# Sheet1.net
KiCad netlist of a schematic drawn in Altium Designer
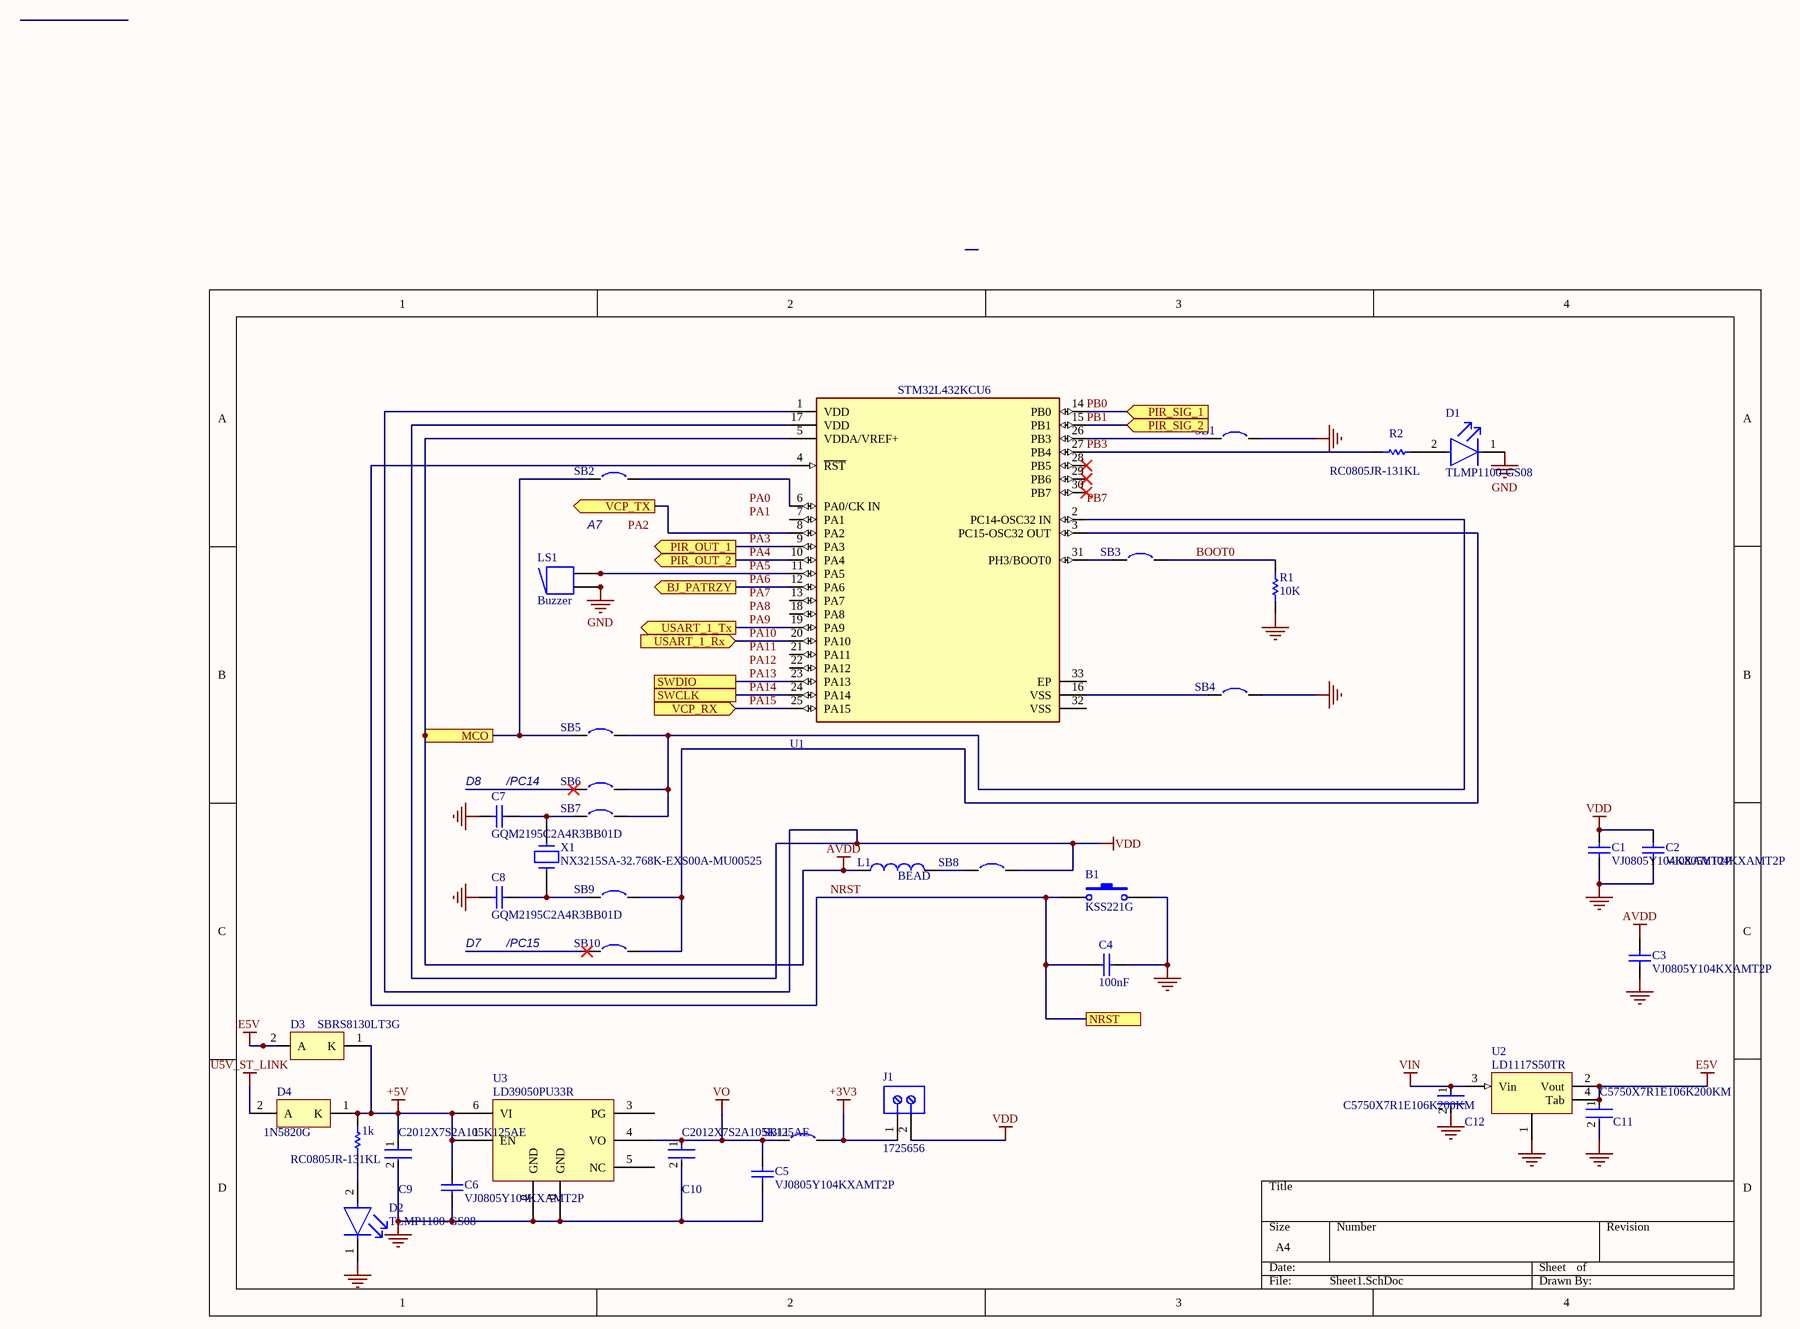
[diagram p0: Sheet1.SchDoc]

(export (version "E")
  (design (tool "Eeschema 10.0.6"))
  (components
    (comp (ref "1k")
      (value "RC0805JR-131KL")
      (footprint "RESC2013X60X35ML10T20")
      (fields (field (name "MANUFACTURER") "Yageo"))
      (libsource (lib "Altium Content Vault") (part "RES"))
    )
    (comp (ref "B1")
      (value "KSS221G")
      (footprint "SW2_5R6_5R5x3R1")
      (description "Switch")
      (fields (field (name "PUBLISHER") "Altium Limited"))
      (libsource (lib "Miscellaneous Devices") (part "SW-PB"))
    )
    (comp (ref "C1")
      (value "VJ0805Y104KXAMT2P")
      (footprint "CAPC2013X145X48NL20T23")
      (fields (field (name "MANUFACTURER") "Vishay"))
      (libsource (lib "Altium Content Vault") (part "CMP-2007-02027-1"))
    )
    (comp (ref "C2")
      (value "VJ0805Y104KXAMT2P")
      (footprint "CAPC2013X145X48NL20T23")
      (fields (field (name "MANUFACTURER") "Vishay"))
      (libsource (lib "Altium Content Vault") (part "CMP-2007-02027-1"))
    )
    (comp (ref "C3")
      (value "VJ0805Y104KXAMT2P")
      (footprint "CAPC2013X145X48NL20T23")
      (fields (field (name "MANUFACTURER") "Vishay"))
      (libsource (lib "Altium Content Vault") (part "CMP-2007-02027-1"))
    )
    (comp (ref "C4")
      (value "100nF")
      (footprint "0603C")
      (description "Capacitor")
      (fields (field (name "PUBLISHER") "Altium Limited"))
      (libsource (lib "Miscellaneous Devices") (part "CAP"))
    )
    (comp (ref "C5")
      (value "VJ0805Y104KXAMT2P")
      (footprint "CAPC2013X145X48NL20T23")
      (fields (field (name "MANUFACTURER") "Vishay"))
      (libsource (lib "Altium Content Vault") (part "CMP-2007-02027-1"))
    )
    (comp (ref "C6")
      (value "VJ0805Y104KXAMT2P")
      (footprint "CAPC2013X145X48NL20T23")
      (fields (field (name "MANUFACTURER") "Vishay"))
      (libsource (lib "Altium Content Vault") (part "CMP-2007-02027-1"))
    )
    (comp (ref "C7")
      (value "GQM2195C2A4R3BB01D")
      (footprint "CAPC2013X100X45LL15T25")
      (fields (field (name "MANUFACTURER") "Murata"))
      (libsource (lib "Altium Content Vault") (part "CMP-2007-03772-1"))
    )
    (comp (ref "C8")
      (value "GQM2195C2A4R3BB01D")
      (footprint "CAPC2013X100X45LL15T25")
      (fields (field (name "MANUFACTURER") "Murata"))
      (libsource (lib "Altium Content Vault") (part "CMP-2007-03772-1"))
    )
    (comp (ref "C9")
      (value "C2012X7S2A105K125AE")
      (footprint "FP-C2012-125-IPC_B")
      (description "CAP CER 1UF 100V X7S 0805")
      (fields (field (name "TOLERANCE") "10%"))
      (libsource (lib "Altium Content Vault") (part "CMP-08246-004333-1"))
    )
    (comp (ref "C10")
      (value "C2012X7S2A105K125AE")
      (footprint "FP-C2012-125-IPC_B")
      (description "CAP CER 1UF 100V X7S 0805")
      (fields (field (name "TOLERANCE") "10%"))
      (libsource (lib "Altium Content Vault") (part "CMP-08246-004333-1"))
    )
    (comp (ref "C11")
      (value "C5750X7R1E106K200KM")
      (footprint "FP-C5750-200-0_4-IPC_A")
      (description "Multilayer Ceramic Capacitors 10uF ±10% 25V X7R SMD 2220")
      (fields (field (name "TOLERANCE") "10%"))
      (libsource (lib "Altium Content Vault") (part "CMP-08246-006659-1"))
    )
    (comp (ref "C12")
      (value "C5750X7R1E106K200KM")
      (footprint "FP-C5750-200-0_4-IPC_A")
      (description "Multilayer Ceramic Capacitors 10uF ±10% 25V X7R SMD 2220")
      (fields (field (name "TOLERANCE") "10%"))
      (libsource (lib "Altium Content Vault") (part "CMP-08246-006659-1"))
    )
    (comp (ref "D1")
      (value "TLMP1100-GS08")
      (footprint "FP-6_541-5056_01-4-MFG")
      (description "Green 561nm LED Indication - Discrete 2.1V 0603 (1608 Metric)")
      (fields (field (name "MANUFACTURER") "Vishay"))
      (libsource (lib "Altium Content Vault") (part "8706943c75ba83719d021d2fdc84c58"))
    )
    (comp (ref "D2")
      (value "TLMP1100-GS08")
      (footprint "FP-6_541-5056_01-4-MFG")
      (description "LED GREEN 0603 SMD")
      (fields
        (field (name "MANUFACTURER") "Vishay")
        (field (name "OCTOPART") "https://octopart.com/tlmp1100-gs08-vishay-55433993")
      )
      (libsource (lib "Components - 19.01.23 - 11.56") (part "CMP-02520-000009-1"))
    )
    (comp (ref "D3")
      (value "SBRS8130LT3G")
      (footprint "ONSC-SMB-2-403A-03_H_V")
      (description "Schottky Power Rectifier, 2-Pin SMB, Pb-Free, Tape and Reel")
      (fields (field (name "MANUFACTURER") "On Semiconductor"))
      (libsource (lib "Altium Content Vault") (part "CMP-1055-00345-1"))
    )
    (comp (ref "D4")
      (value "1N5820G")
      (footprint "ONSC-AXIAL_LEAD-2-267-05_V")
      (description "Rectifier, 2-Pin Axial_Lead, Pb-Free, Bulk Bag")
      (fields (field (name "MANUFACTURER") "On Semiconductor"))
      (libsource (lib "Altium Content Vault") (part "CMP-1055-00026-1"))
    )
    (comp (ref "J1")
      (value "1725656")
      (footprint "PHOE-1725656-2")
      (description "Male Header, Pitch 2.54 mm, 1 x 2 Position, Height 9 mm, Tail Length 3.5 mm")
      (fields (field (name "MANUFACTURER") "Phoenix Contact"))
      (libsource (lib "Altium Content Vault") (part "CMP-2000-05299-1"))
    )
    (comp (ref "L1")
      (value "BEAD")
      (footprint "0603L")
      (description "Inductor")
      (fields (field (name "PUBLISHER") "Altium Limited"))
      (libsource (lib "Miscellaneous Devices") (part "Inductor"))
    )
    (comp (ref "LS1")
      (value "Buzzer")
      (footprint "ABSM-1574")
      (description "Magnetic Transducer Buzzer")
      (fields (field (name "PUBLISHER") "Altium Limited"))
      (libsource (lib "Miscellaneous Devices") (part "Buzzer"))
    )
    (comp (ref "R1")
      (value "10K")
      (footprint "0603R")
      (description "Resistor")
      (fields (field (name "PUBLISHER") "Altium Limited"))
      (libsource (lib "Miscellaneous Devices") (part "res1"))
    )
    (comp (ref "R2")
      (value "RC0805JR-131KL")
      (footprint "RESC2013X60X35ML10T20")
      (fields (field (name "MANUFACTURER") "Yageo"))
      (libsource (lib "Altium Content Vault") (part "RES"))
    )
    (comp (ref "SB1")
      (value "Circuit Breaker (close)")
      (footprint "SB_0603")
      (description "Circuit Breaker")
      (fields (field (name "PUBLISHER") "Altium Limited"))
      (libsource (lib "MCD_TOOLS") (part "Circuit Breaker"))
    )
    (comp (ref "SB2")
      (value "Circuit Breaker (open)")
      (footprint "SB_0603")
      (description "Circuit Breaker")
      (fields (field (name "PUBLISHER") "Altium Limited"))
      (libsource (lib "MCD_TOOLS") (part "Circuit Breaker"))
    )
    (comp (ref "SB3")
      (value "Circuit Breaker (close)")
      (footprint "SB_0603")
      (description "Circuit Breaker")
      (fields (field (name "PUBLISHER") "Altium Limited"))
      (libsource (lib "MCD_TOOLS") (part "Circuit Breaker"))
    )
    (comp (ref "SB4")
      (value "Circuit Breaker (close)")
      (footprint "SB_0603")
      (description "Circuit Breaker")
      (fields (field (name "PUBLISHER") "Altium Limited"))
      (libsource (lib "MCD_TOOLS") (part "Circuit Breaker"))
    )
    (comp (ref "SB5")
      (value "Circuit Breaker (open)")
      (footprint "SB_0603")
      (description "Circuit Breaker")
      (fields (field (name "PUBLISHER") "Altium Limited"))
      (libsource (lib "MCD_TOOLS") (part "Circuit Breaker"))
    )
    (comp (ref "SB6")
      (value "Circuit Breaker")
      (footprint "SB_0603")
      (fields (field (name "PUBLISHER") "Altium Limited"))
      (libsource (lib "MCD_TOOLS") (part "Circuit Breaker"))
    )
    (comp (ref "SB7")
      (value "Circuit Breaker")
      (footprint "SB_0603")
      (fields (field (name "PUBLISHER") "Altium Limited"))
      (libsource (lib "MCD_TOOLS") (part "Circuit Breaker"))
    )
    (comp (ref "SB8")
      (value "Circuit Breaker (close)")
      (footprint "SB_0603")
      (description "Circuit Breaker")
      (fields (field (name "PUBLISHER") "Altium Limited"))
      (libsource (lib "MCD_TOOLS") (part "Circuit Breaker"))
    )
    (comp (ref "SB9")
      (value "Circuit Breaker")
      (footprint "SB_0603")
      (fields (field (name "PUBLISHER") "Altium Limited"))
      (libsource (lib "MCD_TOOLS") (part "Circuit Breaker"))
    )
    (comp (ref "SB10")
      (value "Circuit Breaker")
      (footprint "SB_0603")
      (fields (field (name "PUBLISHER") "Altium Limited"))
      (libsource (lib "MCD_TOOLS") (part "Circuit Breaker"))
    )
    (comp (ref "SB11")
      (value "Circuit Breaker (close)")
      (footprint "SB_0603")
      (description "Circuit Breaker")
      (fields (field (name "PUBLISHER") "Altium Limited"))
      (libsource (lib "MCD_TOOLS") (part "Circuit Breaker"))
    )
    (comp (ref "U1")
      (value "STM32L432KCU6")
      (footprint "FP-UFQFPN32-A0B8-IPC_C")
      (description "IC MCU 32BIT 256KB FLASH 32QFPN")
      (fields
        (field (name "OCTOPART") "https://octopart.com/stm32l432kcu6-stmicroelectronics-71093510")
        (field (name "MANUFACTURER") "STMicroelectronics")
      )
      (libsource (lib "Altium Content Vault") (part "CMP-12105-000033-1"))
    )
    (comp (ref "U2") (value "LD1117S50TR") (footprint "SOT-223") (libsource (lib "MB1180") (part "LD1117")))
    (comp (ref "U3")
      (value "LD39050PU33R")
      (footprint "DFN6_0R95_3x3_TP")
      (libsource (lib "MB1180") (part "LD39050P"))
    )
    (comp (ref "X1")
      (value "NX3215SA-32.768K-EXS00A-MU00525")
      (footprint "XTAL_2SM_3R2X1R5")
      (description "Crystal")
      (libsource (lib "MB1167") (part "CRYSTAL_32K"))
    )
  )
  (nets
    (net (code "1") (name "+3V3") (class "Default")
      (node (ref "J1") (pin "1") (pinfunction "1_1") (pintype "passive"))
      (node (ref "SB11") (pin "2") (pinfunction "2_2") (pintype "passive"))
    )
    (net (code "2") (name "+5V") (class "Default")
      (node (ref "1k") (pin "2") (pinfunction "2_2") (pintype "passive"))
      (node (ref "C6") (pin "2") (pinfunction "2_2") (pintype "passive"))
      (node (ref "C9") (pin "1") (pinfunction "1_1") (pintype "passive"))
      (node (ref "D3") (pin "1") (pinfunction "K_1") (pintype "passive"))
      (node (ref "D4") (pin "1") (pinfunction "K_1") (pintype "passive"))
      (node (ref "U3") (pin "1") (pinfunction "EN_1") (pintype "passive"))
      (node (ref "U3") (pin "6") (pinfunction "VI_6") (pintype "passive"))
    )
    (net (code "3") (name "/BOOT0") (class "Default")
      (node (ref "R1") (pin "1") (pinfunction "1_1") (pintype "passive"))
      (node (ref "SB3") (pin "2") (pinfunction "2_2") (pintype "passive"))
    )
    (net (code "4") (name "/NRST") (class "Default")
      (node (ref "B1") (pin "1") (pinfunction "1_1") (pintype "passive"))
      (node (ref "C4") (pin "2") (pinfunction "2_2") (pintype "passive"))
      (node (ref "U1") (pin "4") (pinfunction "~{RST}_4") (pintype "input"))
    )
    (net (code "8") (name "/PA3") (class "Default")
      (node (ref "U1") (pin "9") (pinfunction "PA3_9") (pintype "bidirectional"))
    )
    (net (code "9") (name "/PA4") (class "Default")
      (node (ref "U1") (pin "10") (pinfunction "PA4_10") (pintype "bidirectional"))
    )
    (net (code "10") (name "/PA5") (class "Default")
      (node (ref "LS1") (pin "2") (pinfunction "2_2") (pintype "passive"))
      (node (ref "LS1") (pin "2A") (pinfunction "2A_2A") (pintype "passive"))
      (node (ref "U1") (pin "11") (pinfunction "PA5_11") (pintype "bidirectional"))
    )
    (net (code "11") (name "/PA6") (class "Default")
      (node (ref "U1") (pin "12") (pinfunction "PA6_12") (pintype "bidirectional"))
    )
    (net (code "14") (name "/PA9") (class "Default")
      (node (ref "U1") (pin "19") (pinfunction "PA9_19") (pintype "bidirectional"))
    )
    (net (code "15") (name "/PA10") (class "Default")
      (node (ref "U1") (pin "20") (pinfunction "PA10_20") (pintype "bidirectional"))
    )
    (net (code "18") (name "/PA13") (class "Default")
      (node (ref "U1") (pin "23") (pinfunction "PA13_23") (pintype "bidirectional"))
    )
    (net (code "19") (name "/PA14") (class "Default")
      (node (ref "U1") (pin "24") (pinfunction "PA14_24") (pintype "bidirectional"))
    )
    (net (code "20") (name "/PA15") (class "Default")
      (node (ref "U1") (pin "25") (pinfunction "PA15_25") (pintype "bidirectional"))
    )
    (net (code "21") (name "/PB0") (class "Default")
      (node (ref "U1") (pin "14") (pinfunction "PB0_14") (pintype "bidirectional"))
    )
    (net (code "22") (name "/PB1") (class "Default")
      (node (ref "U1") (pin "15") (pinfunction "PB1_15") (pintype "bidirectional"))
    )
    (net (code "23") (name "/PB3") (class "Default")
      (node (ref "R2") (pin "1") (pinfunction "1_1") (pintype "passive"))
      (node (ref "U1") (pin "27") (pinfunction "PB4_27") (pintype "bidirectional"))
    )
    (net (code "25") (name "/VCP_TX") (class "Default")
      (node (ref "U1") (pin "8") (pinfunction "PA2_8") (pintype "bidirectional"))
    )
    (net (code "26") (name "AVDD") (class "Default")
      (node (ref "C3") (pin "2") (pinfunction "2_2") (pintype "passive"))
      (node (ref "L1") (pin "1") (pinfunction "1_1") (pintype "passive"))
      (node (ref "SB2") (pin "1") (pinfunction "1_1") (pintype "passive"))
      (node (ref "SB5") (pin "1") (pinfunction "1_1") (pintype "passive"))
      (node (ref "U1") (pin "5") (pinfunction "VDDA/VREF+_5") (pintype "power_in"))
    )
    (net (code "27") (name "E5V") (class "Default")
      (node (ref "C11") (pin "1") (pinfunction "1_1") (pintype "passive"))
      (node (ref "D3") (pin "2") (pinfunction "A_2") (pintype "passive"))
      (node (ref "U2") (pin "2") (pinfunction "Vout_2") (pintype "power_in"))
      (node (ref "U2") (pin "4") (pinfunction "Tab_4") (pintype "power_in"))
    )
    (net (code "28") (name "GND") (class "Default")
      (node (ref "B1") (pin "2") (pinfunction "2_2") (pintype "passive"))
      (node (ref "C1") (pin "1") (pinfunction "1_1") (pintype "passive"))
      (node (ref "C10") (pin "2") (pinfunction "2_2") (pintype "passive"))
      (node (ref "C11") (pin "2") (pinfunction "2_2") (pintype "passive"))
      (node (ref "C12") (pin "2") (pinfunction "2_2") (pintype "passive"))
      (node (ref "C2") (pin "1") (pinfunction "1_1") (pintype "passive"))
      (node (ref "C3") (pin "1") (pinfunction "1_1") (pintype "passive"))
      (node (ref "C4") (pin "1") (pinfunction "1_1") (pintype "passive"))
      (node (ref "C5") (pin "1") (pinfunction "1_1") (pintype "passive"))
      (node (ref "C6") (pin "1") (pinfunction "1_1") (pintype "passive"))
      (node (ref "C7") (pin "1") (pinfunction "1_1") (pintype "passive"))
      (node (ref "C8") (pin "1") (pinfunction "1_1") (pintype "passive"))
      (node (ref "C9") (pin "2") (pinfunction "2_2") (pintype "passive"))
      (node (ref "D1") (pin "1") (pinfunction "C_1") (pintype "passive"))
      (node (ref "D2") (pin "1") (pinfunction "C_1") (pintype "passive"))
      (node (ref "LS1") (pin "1") (pinfunction "1_1") (pintype "passive"))
      (node (ref "LS1") (pin "1A") (pinfunction "1A_1A") (pintype "passive"))
      (node (ref "R1") (pin "2") (pinfunction "2_2") (pintype "passive"))
      (node (ref "SB1") (pin "2") (pinfunction "2_2") (pintype "passive"))
      (node (ref "SB4") (pin "2") (pinfunction "2_2") (pintype "passive"))
      (node (ref "U2") (pin "1") (pintype "passive"))
      (node (ref "U3") (pin "0") (pinfunction "GND_0") (pintype "passive"))
      (node (ref "U3") (pin "2") (pinfunction "GND_2") (pintype "passive"))
    )
    (net (code "29") (name "Net-(C7-Pad2)") (class "Default")
      (node (ref "C7") (pin "2") (pinfunction "2_2") (pintype "passive"))
      (node (ref "SB7") (pin "1") (pinfunction "1_1") (pintype "passive"))
      (node (ref "X1") (pin "1") (pinfunction "1_1") (pintype "passive"))
    )
    (net (code "30") (name "Net-(C8-Pad2)") (class "Default")
      (node (ref "C8") (pin "2") (pinfunction "2_2") (pintype "passive"))
      (node (ref "SB9") (pin "1") (pinfunction "1_1") (pintype "passive"))
      (node (ref "X1") (pin "2") (pinfunction "2_2") (pintype "passive"))
    )
    (net (code "31") (name "Net-(D1-A)") (class "Default")
      (node (ref "D1") (pin "2") (pinfunction "A_2") (pintype "passive"))
      (node (ref "R2") (pin "2") (pinfunction "2_2") (pintype "passive"))
    )
    (net (code "32") (name "Net-(D2-A)") (class "Default")
      (node (ref "1k") (pin "1") (pinfunction "1_1") (pintype "passive"))
      (node (ref "D2") (pin "2") (pinfunction "A_2") (pintype "passive"))
    )
    (net (code "33") (name "Net-(L1-Pad2)") (class "Default")
      (node (ref "L1") (pin "2") (pinfunction "2_2") (pintype "passive"))
      (node (ref "SB8") (pin "1") (pinfunction "1_1") (pintype "passive"))
    )
    (net (code "34") (name "Net-(SB4-Pad1)") (class "Default")
      (node (ref "SB4") (pin "1") (pinfunction "1_1") (pintype "passive"))
      (node (ref "U1") (pin "16") (pinfunction "VSS_16") (pintype "power_in"))
    )
    (net (code "35") (name "Net-(U1-PA0{slash}CK_IN)") (class "Default")
      (node (ref "SB2") (pin "2") (pinfunction "2_2") (pintype "passive"))
      (node (ref "U1") (pin "6") (pinfunction "PA0/CK_IN_6") (pintype "bidirectional"))
    )
    (net (code "36") (name "Net-(U1-PB3)") (class "Default")
      (node (ref "SB1") (pin "1") (pinfunction "1_1") (pintype "passive"))
      (node (ref "U1") (pin "26") (pinfunction "PB3_26") (pintype "bidirectional"))
    )
    (net (code "37") (name "Net-(U1-PC14-OSC32_IN)") (class "Default")
      (node (ref "SB5") (pin "2") (pinfunction "2_2") (pintype "passive"))
      (node (ref "SB6") (pin "2") (pinfunction "2_2") (pintype "passive"))
      (node (ref "SB7") (pin "2") (pinfunction "2_2") (pintype "passive"))
      (node (ref "U1") (pin "2") (pinfunction "PC14-OSC32_IN_2") (pintype "bidirectional"))
    )
    (net (code "38") (name "Net-(U1-PC15-OSC32_OUT)") (class "Default")
      (node (ref "SB10") (pin "2") (pinfunction "2_2") (pintype "passive"))
      (node (ref "SB9") (pin "2") (pinfunction "2_2") (pintype "passive"))
      (node (ref "U1") (pin "3") (pinfunction "PC15-OSC32_OUT_3") (pintype "bidirectional"))
    )
    (net (code "39") (name "Net-(U1-PH3{slash}BOOT0)") (class "Default")
      (node (ref "SB3") (pin "1") (pinfunction "1_1") (pintype "passive"))
      (node (ref "U1") (pin "31") (pinfunction "PH3/BOOT0_31") (pintype "bidirectional"))
    )
    (net (code "40") (name "U5V_ST_LINK") (class "Default")
      (node (ref "D4") (pin "2") (pinfunction "A_2") (pintype "passive"))
    )
    (net (code "41") (name "VDD") (class "Default")
      (node (ref "C1") (pin "2") (pinfunction "2_2") (pintype "passive"))
      (node (ref "C2") (pin "2") (pinfunction "2_2") (pintype "passive"))
      (node (ref "J1") (pin "2") (pinfunction "2_2") (pintype "passive"))
      (node (ref "SB8") (pin "2") (pinfunction "2_2") (pintype "passive"))
      (node (ref "U1") (pin "1") (pinfunction "VDD_1") (pintype "power_in"))
      (node (ref "U1") (pin "17") (pinfunction "VDD_17") (pintype "power_in"))
    )
    (net (code "42") (name "VIN") (class "Default")
      (node (ref "C12") (pin "1") (pinfunction "1_1") (pintype "passive"))
      (node (ref "U2") (pin "3") (pinfunction "Vin_3") (pintype "input"))
    )
    (net (code "43") (name "VO") (class "Default")
      (node (ref "C10") (pin "1") (pinfunction "1_1") (pintype "passive"))
      (node (ref "C5") (pin "2") (pinfunction "2_2") (pintype "passive"))
      (node (ref "SB11") (pin "1") (pinfunction "1_1") (pintype "passive"))
      (node (ref "U3") (pin "4") (pinfunction "VO_4") (pintype "passive"))
    )
    (net (code "44") (name "unconnected-(SB6-Pad1)") (class "Default")
      (node (ref "SB6") (pin "1") (pinfunction "1_1") (pintype "passive+no_connect"))
    )
    (net (code "45") (name "unconnected-(SB10-Pad1)") (class "Default")
      (node (ref "SB10") (pin "1") (pinfunction "1_1") (pintype "passive+no_connect"))
    )
    (net (code "46") (name "unconnected-(U1-EP-Pad33)") (class "Default")
      (node (ref "U1") (pin "33") (pinfunction "EP_33") (pintype "power_in"))
    )
    (net (code "47") (name "unconnected-(U1-PA1-Pad7)") (class "Default")
      (node (ref "U1") (pin "7") (pinfunction "PA1_7") (pintype "bidirectional"))
    )
    (net (code "48") (name "unconnected-(U1-PA7-Pad13)") (class "Default")
      (node (ref "U1") (pin "13") (pinfunction "PA7_13") (pintype "bidirectional"))
    )
    (net (code "49") (name "unconnected-(U1-PA8-Pad18)") (class "Default")
      (node (ref "U1") (pin "18") (pinfunction "PA8_18") (pintype "bidirectional"))
    )
    (net (code "50") (name "unconnected-(U1-PA11-Pad21)") (class "Default")
      (node (ref "U1") (pin "21") (pinfunction "PA11_21") (pintype "bidirectional"))
    )
    (net (code "51") (name "unconnected-(U1-PA12-Pad22)") (class "Default")
      (node (ref "U1") (pin "22") (pinfunction "PA12_22") (pintype "bidirectional"))
    )
    (net (code "52") (name "unconnected-(U1-PB5-Pad28)") (class "Default")
      (node (ref "U1") (pin "28") (pinfunction "PB5_28") (pintype "bidirectional+no_connect"))
    )
    (net (code "53") (name "unconnected-(U1-PB6-Pad29)") (class "Default")
      (node (ref "U1") (pin "29") (pinfunction "PB6_29") (pintype "bidirectional+no_connect"))
    )
    (net (code "54") (name "unconnected-(U1-PB7-Pad30)") (class "Default")
      (node (ref "U1") (pin "30") (pinfunction "PB7_30") (pintype "bidirectional+no_connect"))
    )
    (net (code "55") (name "unconnected-(U1-VSS-Pad32)") (class "Default")
      (node (ref "U1") (pin "32") (pinfunction "VSS_32") (pintype "power_in"))
    )
    (net (code "56") (name "unconnected-(U3-NC-Pad5)") (class "Default")
      (node (ref "U3") (pin "5") (pinfunction "NC_5") (pintype "passive"))
    )
    (net (code "57") (name "unconnected-(U3-PG-Pad3)") (class "Default")
      (node (ref "U3") (pin "3") (pinfunction "PG_3") (pintype "passive"))
    )
  )
)
